# avr_modem.net
KiCad netlist of a schematic drawn in EAGLE
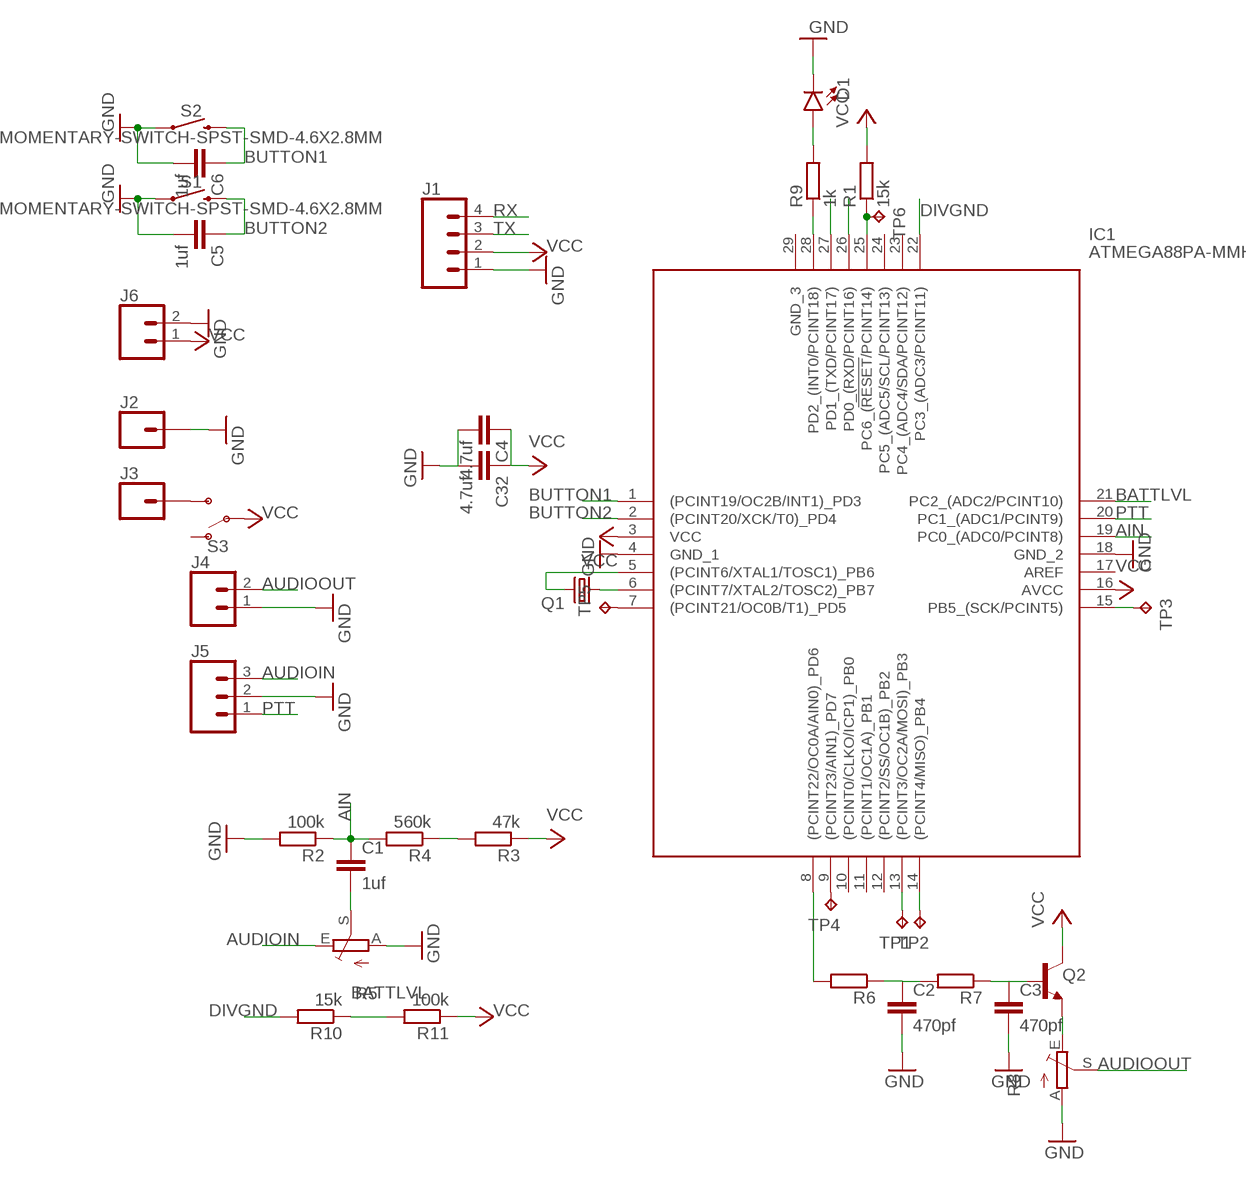
[diagram p0: schematic, sheet 1]

(export (version "E")
  (design (tool "Eeschema 10.0.6"))
  (components
    (comp (ref "C1")
      (value "1uf")
      (footprint "eagle-import:C0805")
      (libsource (lib "eagle-import") (part "C-EUC0805"))
    )
    (comp (ref "C2")
      (value "470pf")
      (footprint "eagle-import:C0805")
      (libsource (lib "eagle-import") (part "C-EUC0805"))
    )
    (comp (ref "C3")
      (value "470pf")
      (footprint "eagle-import:C0805")
      (libsource (lib "eagle-import") (part "C-EUC0805"))
    )
    (comp (ref "C4")
      (value "4.7uf")
      (footprint "eagle-import:C0805")
      (libsource (lib "eagle-import") (part "C-EUC0805"))
    )
    (comp (ref "C5")
      (value "1uf")
      (footprint "eagle-import:C0805")
      (libsource (lib "eagle-import") (part "C-EUC0805"))
    )
    (comp (ref "C6")
      (value "1uf")
      (footprint "eagle-import:C0805")
      (libsource (lib "eagle-import") (part "C-EUC0805"))
    )
    (comp (ref "C32")
      (value "4.7uf")
      (footprint "eagle-import:C0805")
      (libsource (lib "eagle-import") (part "C-EUC0805"))
    )
    (comp (ref "D1")
      (value "LED0603")
      (footprint "eagle-import:LED-0603")
      (libsource (lib "eagle-import") (part "LED0603"))
    )
    (comp (ref "IC1")
      (value "ATMEGA88PA-MMH")
      (footprint "eagle-import:QFN45P400X400X100-29N")
      (fields (field (name "MOUSER_PART_NUMBER") "556-ATMEGA88PA-MMH"))
      (libsource (lib "eagle-import") (part "ATMEGA88PA-MMH"))
    )
    (comp (ref "J1")
      (value "CONN_04LONGPADS")
      (footprint "eagle-import:1X04_LONGPADS")
      (libsource (lib "eagle-import") (part "CONN_04LONGPADS"))
    )
    (comp (ref "J2")
      (value "CONN_01PTH_LONGPAD")
      (footprint "eagle-import:1X01_LONGPAD")
      (libsource (lib "eagle-import") (part "CONN_01PTH_LONGPAD"))
    )
    (comp (ref "J3")
      (value "CONN_01PTH_LONGPAD")
      (footprint "eagle-import:1X01_LONGPAD")
      (libsource (lib "eagle-import") (part "CONN_01PTH_LONGPAD"))
    )
    (comp (ref "J4")
      (value "CONN_02PTH3")
      (footprint "eagle-import:1X02_LONGPADS")
      (libsource (lib "eagle-import") (part "CONN_02PTH3"))
    )
    (comp (ref "J5")
      (value "CONN_03LONGPADS")
      (footprint "eagle-import:1X03_LONGPADS")
      (libsource (lib "eagle-import") (part "CONN_03LONGPADS"))
    )
    (comp (ref "J6")
      (value "CONN_02PTH3")
      (footprint "eagle-import:1X02_LONGPADS")
      (libsource (lib "eagle-import") (part "CONN_02PTH3"))
    )
    (comp (ref "Q1")
      (value "CRYSTALCTS406")
      (footprint "eagle-import:CTS406")
      (libsource (lib "eagle-import") (part "CRYSTALCTS406"))
    )
    (comp (ref "Q2")
      (value "TRANS_NPN-MMBTA42")
      (footprint "eagle-import:SOT23-3")
      (libsource (lib "eagle-import") (part "TRANS_NPN-MMBTA42"))
    )
    (comp (ref "R1")
      (value "15k")
      (footprint "eagle-import:M0805")
      (libsource (lib "eagle-import") (part "R-EU_M0805"))
    )
    (comp (ref "R2")
      (value "100k")
      (footprint "eagle-import:M0805")
      (libsource (lib "eagle-import") (part "R-EU_M0805"))
    )
    (comp (ref "R3")
      (value "47k")
      (footprint "eagle-import:M0805")
      (libsource (lib "eagle-import") (part "R-EU_M0805"))
    )
    (comp (ref "R4")
      (value "560k")
      (footprint "eagle-import:M0805")
      (libsource (lib "eagle-import") (part "R-EU_M0805"))
    )
    (comp (ref "R5")
      (value "TRIM_EU-CA6V")
      (footprint "eagle-import:CA6V")
      (libsource (lib "eagle-import") (part "TRIM_EU-CA6V"))
    )
    (comp (ref "R6")
      (value "R-EU_M0805")
      (footprint "eagle-import:M0805")
      (libsource (lib "eagle-import") (part "R-EU_M0805"))
    )
    (comp (ref "R7")
      (value "R-EU_M0805")
      (footprint "eagle-import:M0805")
      (libsource (lib "eagle-import") (part "R-EU_M0805"))
    )
    (comp (ref "R8")
      (value "TRIM_EU-CA6V")
      (footprint "eagle-import:CA6V")
      (libsource (lib "eagle-import") (part "TRIM_EU-CA6V"))
    )
    (comp (ref "R9")
      (value "1k")
      (footprint "eagle-import:M0805")
      (libsource (lib "eagle-import") (part "R-EU_M0805"))
    )
    (comp (ref "R10")
      (value "15k")
      (footprint "eagle-import:M0805")
      (libsource (lib "eagle-import") (part "R-EU_M0805"))
    )
    (comp (ref "R11")
      (value "100k")
      (footprint "eagle-import:M0805")
      (libsource (lib "eagle-import") (part "R-EU_M0805"))
    )
    (comp (ref "S1")
      (value "MOMENTARY-SWITCH-SPST-SMD-4.6X2.8MM")
      (footprint "eagle-import:TACTILE_SWITCH_SMD_4.6X2.8MM")
      (libsource (lib "eagle-import") (part "MOMENTARY-SWITCH-SPST-SMD-4.6X2.8MM"))
    )
    (comp (ref "S2")
      (value "MOMENTARY-SWITCH-SPST-SMD-4.6X2.8MM")
      (footprint "eagle-import:TACTILE_SWITCH_SMD_4.6X2.8MM")
      (libsource (lib "eagle-import") (part "MOMENTARY-SWITCH-SPST-SMD-4.6X2.8MM"))
    )
    (comp (ref "S3")
      (value "SWITCH-SPDT-SMD-RIGHT-ANGLE")
      (footprint "eagle-import:SWITCH_SPST_SMD_A")
      (libsource (lib "eagle-import") (part "SWITCH-SPDT-SMD-RIGHT-ANGLE"))
    )
    (comp (ref "TP1")
      (value "TPTP15R")
      (footprint "eagle-import:TP15R")
      (libsource (lib "eagle-import") (part "TPTP15R"))
    )
    (comp (ref "TP2")
      (value "TPTP15R")
      (footprint "eagle-import:TP15R")
      (libsource (lib "eagle-import") (part "TPTP15R"))
    )
    (comp (ref "TP3")
      (value "TPTP15R")
      (footprint "eagle-import:TP15R")
      (libsource (lib "eagle-import") (part "TPTP15R"))
    )
    (comp (ref "TP4")
      (value "TPTP15R")
      (footprint "eagle-import:TP15R")
      (libsource (lib "eagle-import") (part "TPTP15R"))
    )
    (comp (ref "TP5")
      (value "TPTP15R")
      (footprint "eagle-import:TP15R")
      (libsource (lib "eagle-import") (part "TPTP15R"))
    )
    (comp (ref "TP6")
      (value "TPTP15R")
      (footprint "eagle-import:TP15R")
      (libsource (lib "eagle-import") (part "TPTP15R"))
    )
  )
  (nets
    (net (code "1") (name "/AIN") (class "Default")
      (node (ref "C1") (pin "1") (pinfunction "1_1") (pintype "passive"))
      (node (ref "IC1") (pin "19") (pinfunction "PC0_(ADC0/PCINT8)_19") (pintype "bidirectional"))
      (node (ref "R2") (pin "1") (pinfunction "1_1") (pintype "passive"))
      (node (ref "R4") (pin "2") (pinfunction "2_2") (pintype "passive"))
    )
    (net (code "2") (name "/AUDIOIN") (class "Default")
      (node (ref "J5") (pin "3") (pinfunction "3_3") (pintype "passive"))
      (node (ref "R5") (pin "E") (pinfunction "E_E") (pintype "passive"))
    )
    (net (code "3") (name "/AUDIOOUT") (class "Default")
      (node (ref "J4") (pin "2") (pinfunction "2_2") (pintype "passive"))
      (node (ref "R8") (pin "S") (pinfunction "S_S") (pintype "passive"))
    )
    (net (code "4") (name "/BATTLVL") (class "Default")
      (node (ref "IC1") (pin "21") (pinfunction "PC2_(ADC2/PCINT10)_21") (pintype "bidirectional"))
      (node (ref "R10") (pin "1") (pinfunction "1_1") (pintype "passive"))
      (node (ref "R11") (pin "2") (pinfunction "2_2") (pintype "passive"))
    )
    (net (code "5") (name "/BUTTON1") (class "Default")
      (node (ref "C6") (pin "1") (pinfunction "1_1") (pintype "passive"))
      (node (ref "IC1") (pin "1") (pinfunction "(PCINT19/OC2B/INT1)_PD3_1") (pintype "bidirectional"))
      (node (ref "S2") (pin "3") (pinfunction "2_3") (pintype "passive"))
      (node (ref "S2") (pin "4") (pinfunction "2_4") (pintype "passive"))
    )
    (net (code "6") (name "/BUTTON2") (class "Default")
      (node (ref "C5") (pin "1") (pinfunction "1_1") (pintype "passive"))
      (node (ref "IC1") (pin "2") (pinfunction "(PCINT20/XCK/T0)_PD4_2") (pintype "bidirectional"))
      (node (ref "S1") (pin "3") (pinfunction "2_3") (pintype "passive"))
      (node (ref "S1") (pin "4") (pinfunction "2_4") (pintype "passive"))
    )
    (net (code "7") (name "/DIVGND") (class "Default")
      (node (ref "IC1") (pin "22") (pinfunction "PC3_(ADC3/PCINT11)_22") (pintype "bidirectional"))
      (node (ref "R10") (pin "2") (pinfunction "2_2") (pintype "passive"))
    )
    (net (code "8") (name "/PTT") (class "Default")
      (node (ref "IC1") (pin "20") (pinfunction "PC1_(ADC1/PCINT9)_20") (pintype "bidirectional"))
      (node (ref "J5") (pin "1") (pinfunction "1_1") (pintype "passive"))
    )
    (net (code "9") (name "/RX") (class "Default")
      (node (ref "IC1") (pin "26") (pinfunction "PD0_(RXD/PCINT16)_26") (pintype "bidirectional"))
      (node (ref "J1") (pin "4") (pinfunction "4_4") (pintype "passive"))
    )
    (net (code "10") (name "/TX") (class "Default")
      (node (ref "IC1") (pin "27") (pinfunction "PD1_(TXD/PCINT17)_27") (pintype "bidirectional"))
      (node (ref "J1") (pin "3") (pinfunction "3_3") (pintype "passive"))
    )
    (net (code "11") (name "GND") (class "Default")
      (node (ref "C2") (pin "2") (pinfunction "2_2") (pintype "passive"))
      (node (ref "C3") (pin "2") (pinfunction "2_2") (pintype "passive"))
      (node (ref "C32") (pin "2") (pinfunction "2_2") (pintype "passive"))
      (node (ref "C4") (pin "2") (pinfunction "2_2") (pintype "passive"))
      (node (ref "C5") (pin "2") (pinfunction "2_2") (pintype "passive"))
      (node (ref "C6") (pin "2") (pinfunction "2_2") (pintype "passive"))
      (node (ref "D1") (pin "C") (pinfunction "C_C") (pintype "passive"))
      (node (ref "IC1") (pin "18") (pinfunction "GND_2_18") (pintype "bidirectional"))
      (node (ref "IC1") (pin "4") (pinfunction "GND_1_4") (pintype "bidirectional"))
      (node (ref "J1") (pin "1") (pinfunction "1_1") (pintype "passive"))
      (node (ref "J2") (pin "1") (pinfunction "1_1") (pintype "passive"))
      (node (ref "J4") (pin "1") (pinfunction "1_1") (pintype "passive"))
      (node (ref "J5") (pin "2") (pinfunction "2_2") (pintype "passive"))
      (node (ref "J6") (pin "2") (pinfunction "2_2") (pintype "passive"))
      (node (ref "R2") (pin "2") (pinfunction "2_2") (pintype "passive"))
      (node (ref "R5") (pin "A") (pinfunction "A_A") (pintype "passive"))
      (node (ref "R8") (pin "A") (pinfunction "A_A") (pintype "passive"))
      (node (ref "S1") (pin "1") (pinfunction "1_1") (pintype "passive"))
      (node (ref "S1") (pin "2") (pinfunction "1_2") (pintype "passive"))
      (node (ref "S2") (pin "1") (pinfunction "1_1") (pintype "passive"))
      (node (ref "S2") (pin "2") (pinfunction "1_2") (pintype "passive"))
    )
    (net (code "12") (name "Net-(C1-Pad2)") (class "Default")
      (node (ref "C1") (pin "2") (pinfunction "2_2") (pintype "passive"))
      (node (ref "R5") (pin "S") (pinfunction "S_S") (pintype "passive"))
    )
    (net (code "13") (name "Net-(C2-Pad1)") (class "Default")
      (node (ref "C2") (pin "1") (pinfunction "1_1") (pintype "passive"))
      (node (ref "R6") (pin "1") (pinfunction "1_1") (pintype "passive"))
      (node (ref "R7") (pin "2") (pinfunction "2_2") (pintype "passive"))
    )
    (net (code "14") (name "Net-(D1-PadA)") (class "Default")
      (node (ref "D1") (pin "A") (pinfunction "A_A") (pintype "passive"))
      (node (ref "R9") (pin "2") (pinfunction "2_2") (pintype "passive"))
    )
    (net (code "15") (name "Net-(IC1-(PCINT3{slash}OC2A{slash}MOSI)_PB3)") (class "Default")
      (node (ref "IC1") (pin "13") (pinfunction "(PCINT3/OC2A/MOSI)_PB3_13") (pintype "bidirectional"))
      (node (ref "TP1") (pin "TP") (pinfunction "TP_TP") (pintype "input"))
    )
    (net (code "16") (name "Net-(IC1-(PCINT4{slash}MISO)_PB4)") (class "Default")
      (node (ref "IC1") (pin "14") (pinfunction "(PCINT4/MISO)_PB4_14") (pintype "bidirectional"))
      (node (ref "TP2") (pin "TP") (pinfunction "TP_TP") (pintype "input"))
    )
    (net (code "17") (name "Net-(IC1-(PCINT6{slash}XTAL1{slash}TOSC1)_PB6)") (class "Default")
      (node (ref "IC1") (pin "5") (pinfunction "(PCINT6/XTAL1/TOSC1)_PB6_5") (pintype "bidirectional"))
      (node (ref "Q1") (pin "3") (pinfunction "2_3") (pintype "passive"))
    )
    (net (code "18") (name "Net-(IC1-(PCINT7{slash}XTAL2{slash}TOSC2)_PB7)") (class "Default")
      (node (ref "IC1") (pin "6") (pinfunction "(PCINT7/XTAL2/TOSC2)_PB7_6") (pintype "bidirectional"))
      (node (ref "Q1") (pin "1") (pinfunction "1_1") (pintype "passive"))
    )
    (net (code "19") (name "Net-(IC1-(PCINT21{slash}OC0B{slash}T1)_PD5)") (class "Default")
      (node (ref "IC1") (pin "7") (pinfunction "(PCINT21/OC0B/T1)_PD5_7") (pintype "bidirectional"))
      (node (ref "TP5") (pin "TP") (pinfunction "TP_TP") (pintype "input"))
    )
    (net (code "20") (name "Net-(IC1-(PCINT22{slash}OC0A{slash}AIN0)_PD6)") (class "Default")
      (node (ref "IC1") (pin "8") (pinfunction "(PCINT22/OC0A/AIN0)_PD6_8") (pintype "bidirectional"))
      (node (ref "R6") (pin "2") (pinfunction "2_2") (pintype "passive"))
    )
    (net (code "21") (name "Net-(IC1-(PCINT23{slash}AIN1)_PD7)") (class "Default")
      (node (ref "IC1") (pin "9") (pinfunction "(PCINT23/AIN1)_PD7_9") (pintype "bidirectional"))
      (node (ref "TP4") (pin "TP") (pinfunction "TP_TP") (pintype "input"))
    )
    (net (code "22") (name "Net-(IC1-PB5_(SCK{slash}PCINT5))") (class "Default")
      (node (ref "IC1") (pin "15") (pinfunction "PB5_(SCK/PCINT5)_15") (pintype "bidirectional"))
      (node (ref "TP3") (pin "TP") (pinfunction "TP_TP") (pintype "input"))
    )
    (net (code "23") (name "Net-(IC1-PC6_(~{RESET}{slash}PCINT14))") (class "Default")
      (node (ref "IC1") (pin "25") (pinfunction "PC6_(~{RESET}/PCINT14)_25") (pintype "bidirectional"))
      (node (ref "R1") (pin "1") (pinfunction "1_1") (pintype "passive"))
      (node (ref "TP6") (pin "TP") (pinfunction "TP_TP") (pintype "input"))
    )
    (net (code "24") (name "Net-(IC1-PD2_(INT0{slash}PCINT18))") (class "Default")
      (node (ref "IC1") (pin "28") (pinfunction "PD2_(INT0/PCINT18)_28") (pintype "bidirectional"))
      (node (ref "R9") (pin "1") (pinfunction "1_1") (pintype "passive"))
    )
    (net (code "25") (name "Net-(Q2-B)") (class "Default")
      (node (ref "C3") (pin "1") (pinfunction "1_1") (pintype "passive"))
      (node (ref "Q2") (pin "1") (pinfunction "B_1") (pintype "passive"))
      (node (ref "R7") (pin "1") (pinfunction "1_1") (pintype "passive"))
    )
    (net (code "26") (name "Net-(Q2-E)") (class "Default")
      (node (ref "Q2") (pin "2") (pinfunction "E_2") (pintype "passive"))
      (node (ref "R8") (pin "E") (pinfunction "E_E") (pintype "passive"))
    )
    (net (code "27") (name "Net-(R3-Pad2)") (class "Default")
      (node (ref "R3") (pin "2") (pinfunction "2_2") (pintype "passive"))
      (node (ref "R4") (pin "1") (pinfunction "1_1") (pintype "passive"))
    )
    (net (code "28") (name "Net-(S3-S)") (class "Default")
      (node (ref "J3") (pin "1") (pinfunction "1_1") (pintype "passive"))
      (node (ref "S3") (pin "3") (pinfunction "S_3") (pintype "passive"))
    )
    (net (code "29") (name "VCC") (class "Default")
      (node (ref "C32") (pin "1") (pinfunction "1_1") (pintype "passive"))
      (node (ref "C4") (pin "1") (pinfunction "1_1") (pintype "passive"))
      (node (ref "IC1") (pin "16") (pinfunction "AVCC_16") (pintype "bidirectional"))
      (node (ref "IC1") (pin "3") (pinfunction "VCC_3") (pintype "bidirectional"))
      (node (ref "J1") (pin "2") (pinfunction "2_2") (pintype "passive"))
      (node (ref "J6") (pin "1") (pinfunction "1_1") (pintype "passive"))
      (node (ref "Q2") (pin "3") (pinfunction "C_3") (pintype "passive"))
      (node (ref "R1") (pin "2") (pinfunction "2_2") (pintype "passive"))
      (node (ref "R11") (pin "1") (pinfunction "1_1") (pintype "passive"))
      (node (ref "R3") (pin "1") (pinfunction "1_1") (pintype "passive"))
      (node (ref "S3") (pin "2") (pinfunction "P_2") (pintype "passive"))
    )
    (net (code "30") (name "unconnected-(IC1-(PCINT0{slash}CLKO{slash}ICP1)_PB0-Pad10)") (class "Default")
      (node (ref "IC1") (pin "10") (pinfunction "(PCINT0/CLKO/ICP1)_PB0_10") (pintype "bidirectional"))
    )
    (net (code "31") (name "unconnected-(IC1-(PCINT1{slash}OC1A)_PB1-Pad11)") (class "Default")
      (node (ref "IC1") (pin "11") (pinfunction "(PCINT1/OC1A)_PB1_11") (pintype "bidirectional"))
    )
    (net (code "32") (name "unconnected-(IC1-(PCINT2{slash}SS{slash}OC1B)_PB2-Pad12)") (class "Default")
      (node (ref "IC1") (pin "12") (pinfunction "(PCINT2/SS/OC1B)_PB2_12") (pintype "bidirectional"))
    )
    (net (code "33") (name "unconnected-(IC1-AREF-Pad17)") (class "Default")
      (node (ref "IC1") (pin "17") (pinfunction "AREF_17") (pintype "bidirectional"))
    )
    (net (code "34") (name "unconnected-(IC1-GND_3-Pad29)") (class "Default")
      (node (ref "IC1") (pin "29") (pinfunction "GND_3_29") (pintype "bidirectional"))
    )
    (net (code "35") (name "unconnected-(IC1-PC4_(ADC4{slash}SDA{slash}PCINT12)-Pad23)") (class "Default")
      (node (ref "IC1") (pin "23") (pinfunction "PC4_(ADC4/SDA/PCINT12)_23") (pintype "bidirectional"))
    )
    (net (code "36") (name "unconnected-(IC1-PC5_(ADC5{slash}SCL{slash}PCINT13)-Pad24)") (class "Default")
      (node (ref "IC1") (pin "24") (pinfunction "PC5_(ADC5/SCL/PCINT13)_24") (pintype "bidirectional"))
    )
    (net (code "37") (name "unconnected-(S3-O-Pad1)") (class "Default")
      (node (ref "S3") (pin "1") (pinfunction "O_1") (pintype "passive"))
    )
  )
)
